# 12V_Buck_For_5V_3V3.net
KiCad netlist of a schematic drawn in Altium Designer
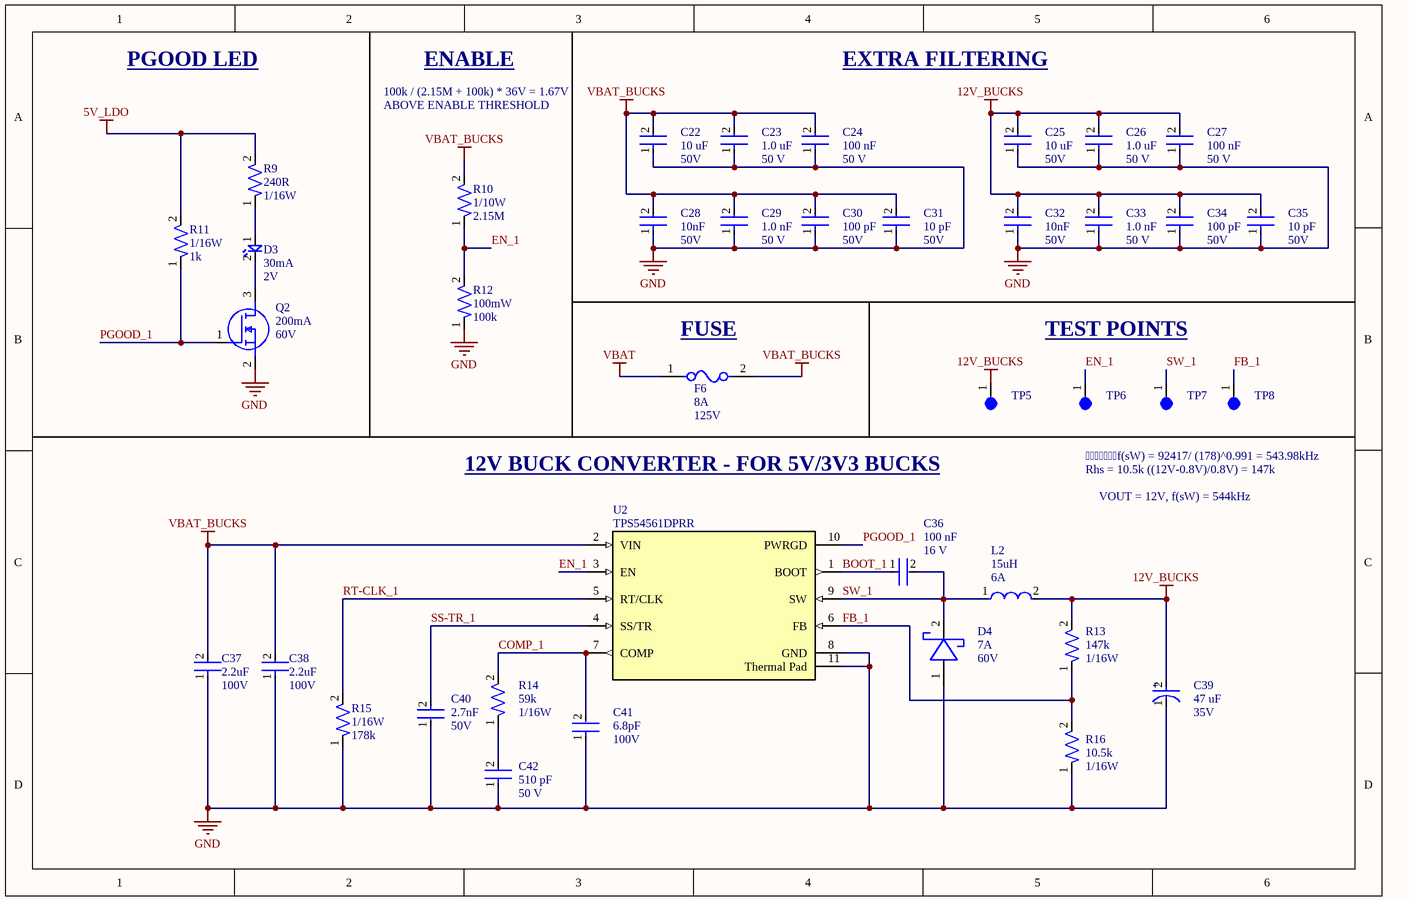
[diagram p0: 12V_Buck_For_5V_3V3.SchDoc]

(export (version "E")
  (design (tool "Eeschema 10.0.6"))
  (components
    (comp (ref "C22")
      (value "CL32B106KBJNNNE")
      (footprint "CAP-1210")
      (description "CAP CER 10UF 50V X7R 1210")
      (fields (field (name "VOLTAGE") "50V") (field (name "CAPACITANCE") "10 uF"))
      (libsource (lib "JLC_25") (part "CAP-10U-0002"))
    )
    (comp (ref "C23")
      (value "CC0805KKX7R9BB105")
      (footprint "CAP-0805")
      (description "CAP CER 1UF 50V X7R 0805")
      (fields (field (name "VOLTAGE") "50 V") (field (name "CAPACITANCE") "1.0 uF"))
      (libsource (lib "JLC_25") (part "CAP-1U-0001"))
    )
    (comp (ref "C24")
      (value "CC0805KRX7R9BB104")
      (footprint "CAP-0805")
      (description "CAP CER 0.1UF 50V X7R 0805")
      (fields (field (name "VOLTAGE RATING") "50 V") (field (name "CAPACITANCE") "100 nF"))
      (libsource (lib "JLC_25") (part "CAP-0.1U-0002"))
    )
    (comp (ref "C25")
      (value "CL32B106KBJNNNE")
      (footprint "CAP-1210")
      (description "CAP CER 10UF 50V X7R 1210")
      (fields (field (name "VOLTAGE") "50V") (field (name "CAPACITANCE") "10 uF"))
      (libsource (lib "JLC_25") (part "CAP-10U-0002"))
    )
    (comp (ref "C26")
      (value "CC0805KKX7R9BB105")
      (footprint "CAP-0805")
      (description "CAP CER 1UF 50V X7R 0805")
      (fields (field (name "VOLTAGE") "50 V") (field (name "CAPACITANCE") "1.0 uF"))
      (libsource (lib "JLC_25") (part "CAP-1U-0001"))
    )
    (comp (ref "C27")
      (value "CC0805KRX7R9BB104")
      (footprint "CAP-0805")
      (description "CAP CER 0.1UF 50V X7R 0805")
      (fields (field (name "VOLTAGE RATING") "50 V") (field (name "CAPACITANCE") "100 nF"))
      (libsource (lib "JLC_25") (part "CAP-0.1U-0002"))
    )
    (comp (ref "C28")
      (value "GRM2195C1H103JA01D")
      (footprint "CAP-0805")
      (description "CAP CER 10000PF 50V C0G/NP0 0805")
      (fields (field (name "VOLTAGE") "50V") (field (name "CAPACITANCE") "10nF"))
      (libsource (lib "JLC_25") (part "CAP-10N-0001"))
    )
    (comp (ref "C29")
      (value "CC0402KRX7R9BB102")
      (footprint "CAP-0402")
      (description "CAP CER 1000PF 50V X7R 0402")
      (fields (field (name "VOLTAGE") "50 V") (field (name "CAPACITANCE") "1.0 nF"))
      (libsource (lib "JLC_25") (part "CAP-1N-0001"))
    )
    (comp (ref "C30")
      (value "CC0402JRNPO9BN101")
      (footprint "CAP-0402")
      (description "CAP CER 100PF 50V C0G/NPO 0402")
      (fields (field (name "CAPACITANCE") "100 pF") (field (name "VOLTAGE") "50V"))
      (libsource (lib "JLC_25") (part "CAP-100P-0001"))
    )
    (comp (ref "C31")
      (value "CC0402JRNPO9BN100")
      (footprint "CAP-0402")
      (description "CAP CER 10PF 50V C0G/NPO 0402")
      (fields (field (name "CAPACITANCE") "10 pF") (field (name "VOLTAGE") "50V"))
      (libsource (lib "JLC_25") (part "CAP-10P-0001"))
    )
    (comp (ref "C32")
      (value "GRM2195C1H103JA01D")
      (footprint "CAP-0805")
      (description "CAP CER 10000PF 50V C0G/NP0 0805")
      (fields (field (name "VOLTAGE") "50V") (field (name "CAPACITANCE") "10nF"))
      (libsource (lib "JLC_25") (part "CAP-10N-0001"))
    )
    (comp (ref "C33")
      (value "CC0402KRX7R9BB102")
      (footprint "CAP-0402")
      (description "CAP CER 1000PF 50V X7R 0402")
      (fields (field (name "VOLTAGE") "50 V") (field (name "CAPACITANCE") "1.0 nF"))
      (libsource (lib "JLC_25") (part "CAP-1N-0001"))
    )
    (comp (ref "C34")
      (value "CC0402JRNPO9BN101")
      (footprint "CAP-0402")
      (description "CAP CER 100PF 50V C0G/NPO 0402")
      (fields (field (name "CAPACITANCE") "100 pF") (field (name "VOLTAGE") "50V"))
      (libsource (lib "JLC_25") (part "CAP-100P-0001"))
    )
    (comp (ref "C35")
      (value "CC0402JRNPO9BN100")
      (footprint "CAP-0402")
      (description "CAP CER 10PF 50V C0G/NPO 0402")
      (fields (field (name "CAPACITANCE") "10 pF") (field (name "VOLTAGE") "50V"))
      (libsource (lib "JLC_25") (part "CAP-10P-0001"))
    )
    (comp (ref "C36")
      (value "CC0402KRX7R7BB104")
      (footprint "CAP-0402")
      (description "CAP CER 0.1UF 16V X7R 0402")
      (fields (field (name "VOLTAGE RATING") "16 V") (field (name "CAPACITANCE") "100 nF"))
      (libsource (lib "JLC_25") (part "CAP-0.1U-0001"))
    )
    (comp (ref "C37")
      (value "CC1206KKX7R0BB225")
      (footprint "CAP-1206")
      (description "CAP CER 2.2UF 100V X7R 1206")
      (fields (field (name "CAPACITANCE") "2.2uF") (field (name "VOLTAGE") "100V"))
      (libsource (lib "JLC_25") (part "CAP-2.2U-0001"))
    )
    (comp (ref "C38")
      (value "CC1206KKX7R0BB225")
      (footprint "CAP-1206")
      (description "CAP CER 2.2UF 100V X7R 1206")
      (fields (field (name "CAPACITANCE") "2.2uF") (field (name "VOLTAGE") "100V"))
      (libsource (lib "JLC_25") (part "CAP-2.2U-0001"))
    )
    (comp (ref "C39")
      (value "EEH-ZC1V470P")
      (footprint "CAP_EEHZC1V470P")
      (description "47 µF 35 V Aluminum - Polymer Capacitors Radial, Can - SMD 60mOhm 4000 Hrs @ 125°C")
      (fields (field (name "VOLTAGE") "35V") (field (name "CAPACITANCE") "47 uF"))
      (libsource (lib "JLC_25") (part "CAP-47U-0003"))
    )
    (comp (ref "C40")
      (value "GRM2165C1H272JA01D")
      (footprint "CAP-0805")
      (description "CAP CER 2700PF 50V C0G/NP0 0805")
      (fields (field (name "VOLTAGE") "50V") (field (name "CAPACITANCE") "2.7nF"))
      (libsource (lib "JLC_25") (part "CAP-2.7N-0001"))
    )
    (comp (ref "C41")
      (value "CC0603CRNPO0BN6R8")
      (footprint "CAP-0603")
      (description "CAP CER 6.8PF 100V C0G/NPO 0603")
      (fields (field (name "VOLTAGE") "100V") (field (name "CAPACITANCE") "6.8pF"))
      (libsource (lib "JLC_25") (part "CAP-6.8P-0001"))
    )
    (comp (ref "C42")
      (value "0402N511J500CT")
      (footprint "CAP-0402")
      (description "CAP CER 510PF 50V C0G/NP0 0402")
      (fields (field (name "VOLTAGE") "50 V") (field (name "CAPACITANCE") "510 pF"))
      (libsource (lib "JLC_25") (part "CAP-510P-0001"))
    )
    (comp (ref "D3")
      (value "BL-HKC36G-AV-TRB")
      (footprint "LED-0603")
      (description "LED YELLOW CLEAR 0603 SMD")
      (fields (field (name "FORWARD CURRENT") "30mA") (field (name "FORWARD VOLTAGE") "2V"))
      (libsource (lib "JLC_25") (part "LED-0001"))
    )
    (comp (ref "D4")
      (value "PDS760-13")
      (footprint "DO-POWERDI5")
      (description "DIODE SCHOTTKY 60V 7A POWERDI5")
      (fields (field (name "FORWARD CURRENT") "7A") (field (name "REVERSE VOLTAGE (DC)") "60V"))
      (libsource (lib "JLC_25") (part "DIO-SCHOTTKY-0001"))
    )
    (comp (ref "F6")
      (value "01550900M")
      (footprint "FUSE-0001")
      (description "FUSE BLOK CARTRIDGE 125V 10A SMD")
      (fields (field (name "FUSE CURRENT") "8A") (field (name "VOLTAGE RATING") "125V"))
      (libsource (lib "JLC_25") (part "FUSE-0001"))
    )
    (comp (ref "L2")
      (value "CSAD1010-150M")
      (footprint "IND-15U-0002")
      (description "SMD MOLDING POWER CHOKE")
      (fields (field (name "INDUCTANCE") "15uH") (field (name "CURRENT RATING") "6A"))
      (libsource (lib "JLC_25") (part "IND-15U-0002-NoJLC"))
    )
    (comp (ref "Q2")
      (value "T2N7002AK,LM")
      (footprint "IC-SOT23-3")
      (description "MOSFET N-CH 60V 200MA SOT23")
      (fields (field (name "CONTINUOUS CURRENT") "200mA") (field (name "VOLTAGE") "60V"))
      (libsource (lib "JLC_25") (part "NMOS-200MA-0001"))
    )
    (comp (ref "R9")
      (value "RC0402FR-07240RL")
      (footprint "RES-0402")
      (description "240R 0.063W 1% 0402 (1005 Metric)  SMD")
      (fields
        (field (name "TOLERANCE") "1%")
        (field (name "RESISTANCE") "240R")
        (field (name "POWER") "1/16W")
      )
      (libsource (lib "JLC_25") (part "RES-240-0001"))
    )
    (comp (ref "R10")
      (value "RC0603FR-072M15L")
      (footprint "RES-0603")
      (description "RES SMD 2.15M OHM 1% 1/10W 0603")
      (fields
        (field (name "TOLERANCE") "1%")
        (field (name "POWER") "1/10W")
        (field (name "RESISTANCE") "2.15M")
      )
      (libsource (lib "JLC_25") (part "RES-2.15M-0001"))
    )
    (comp (ref "R11")
      (value "RC0402FR-071KL")
      (footprint "RES-0402")
      (description "RES 1K OHM 1% 1/16W 0402")
      (fields (field (name "TOLERANCE") "1%") (field (name "POWER") "1/16W") (field (name "RESISTANCE") "1k"))
      (libsource (lib "JLC_25") (part "RES-1k-0001"))
    )
    (comp (ref "R12")
      (value "RC0603FR-07100KL")
      (footprint "RES-0603")
      (description "RES SMD 100K OHM 1% 1/10W 0603")
      (fields
        (field (name "TOLERANCE") "1%")
        (field (name "POWER") "100mW")
        (field (name "RESISTANCE") "100k")
      )
      (libsource (lib "JLC_25") (part "RES-100k-0001"))
    )
    (comp (ref "R13")
      (value "RC0402FR-07147KL")
      (footprint "RES-0402")
      (description "RES 147K OHM 1% 1/16W 0402")
      (fields
        (field (name "TOLERANCE") "1%")
        (field (name "POWER") "1/16W")
        (field (name "RESISTANCE") "147k")
      )
      (libsource (lib "JLC_25") (part "RES-147k-0001"))
    )
    (comp (ref "R14")
      (value "RC0402FR-0759KL")
      (footprint "RES-0402")
      (description "RES 59K OHM 1% 1/16W 0402")
      (fields
        (field (name "TOLERANCE") "1%")
        (field (name "POWER") "1/16W")
        (field (name "RESISTANCE") "59k")
      )
      (libsource (lib "JLC_25") (part "RES-59k-0001"))
    )
    (comp (ref "R15")
      (value "RTT021783FTH")
      (footprint "RES-0402")
      (description "62.5mW Thick Film Resistors 50V ±100ppm/℃ ±1% 178kΩ 0402 Chip Resistor - Surface Mount ROHS")
      (fields
        (field (name "TOLERANCE") "1%")
        (field (name "POWER") "1/16W")
        (field (name "RESISTANCE") "178k")
      )
      (libsource (lib "JLC_25") (part "RES-178k-0001_1"))
    )
    (comp (ref "R16")
      (value "RC0402FR-0710K5L")
      (footprint "RES-0402")
      (description "RES 10.5K OHM 1% 1/16W 0402")
      (fields
        (field (name "TOLERANCE") "1%")
        (field (name "POWER") "1/16W")
        (field (name "RESISTANCE") "10.5k")
      )
      (libsource (lib "JLC_25") (part "RES-10.5k-0001"))
    )
    (comp (ref "TP5")
      (value "5003")
      (footprint "TEST-POINT-0001")
      (description "Oranange PC Test Point, Miniature Phoisphor Bronze Silver Plating Through Hole Mounting Type")
      (libsource (lib "*") (part "TEST-POINT-0001"))
    )
    (comp (ref "TP6")
      (value "5003")
      (footprint "TEST-POINT-0001")
      (description "Oranange PC Test Point, Miniature Phoisphor Bronze Silver Plating Through Hole Mounting Type")
      (libsource (lib "*") (part "TEST-POINT-0001"))
    )
    (comp (ref "TP7")
      (value "5003")
      (footprint "TEST-POINT-0001")
      (description "Oranange PC Test Point, Miniature Phoisphor Bronze Silver Plating Through Hole Mounting Type")
      (libsource (lib "*") (part "TEST-POINT-0001"))
    )
    (comp (ref "TP8")
      (value "5003")
      (footprint "TEST-POINT-0001")
      (description "Oranange PC Test Point, Miniature Phoisphor Bronze Silver Plating Through Hole Mounting Type")
      (libsource (lib "*") (part "TEST-POINT-0001"))
    )
    (comp (ref "U2")
      (value "TPS54561DPRR")
      (footprint "IC-10WSON")
      (description "IC REG BUCK ADJ 5A 10WSON")
      (libsource (lib "JLC_25") (part "IC-BUCK-0001"))
    )
  )
  (nets
    (net (code "1") (name "/BOOT_1") (class "Default")
      (node (ref "C36") (pin "1") (pinfunction "1_1") (pintype "passive"))
      (node (ref "U2") (pin "1") (pinfunction "BOOT_1") (pintype "output"))
    )
    (net (code "2") (name "/COMP_1") (class "Default")
      (node (ref "C41") (pin "2") (pinfunction "2_2") (pintype "passive"))
      (node (ref "R14") (pin "2") (pinfunction "2_2") (pintype "passive"))
      (node (ref "U2") (pin "7") (pinfunction "COMP_7") (pintype "output"))
    )
    (net (code "3") (name "/EN_1") (class "Default")
      (node (ref "R10") (pin "1") (pinfunction "1_1") (pintype "passive"))
      (node (ref "R12") (pin "2") (pinfunction "2_2") (pintype "passive"))
      (node (ref "TP6") (pin "1") (pinfunction "0_1") (pintype "passive"))
      (node (ref "U2") (pin "3") (pinfunction "EN_3") (pintype "input"))
    )
    (net (code "4") (name "/FB_1") (class "Default")
      (node (ref "R13") (pin "1") (pinfunction "1_1") (pintype "passive"))
      (node (ref "R16") (pin "2") (pinfunction "2_2") (pintype "passive"))
      (node (ref "TP8") (pin "1") (pinfunction "0_1") (pintype "passive"))
      (node (ref "U2") (pin "6") (pinfunction "FB_6") (pintype "input"))
    )
    (net (code "5") (name "/PGOOD_1") (class "Default")
      (node (ref "Q2") (pin "1") (pinfunction "G_1") (pintype "passive"))
      (node (ref "R11") (pin "1") (pinfunction "1_1") (pintype "passive"))
      (node (ref "U2") (pin "10") (pinfunction "PWRGD_10") (pintype "open_collector"))
    )
    (net (code "6") (name "/RT-CLK_1") (class "Default")
      (node (ref "R15") (pin "2") (pinfunction "2_2") (pintype "passive"))
      (node (ref "U2") (pin "5") (pinfunction "RT/CLK_5") (pintype "input"))
    )
    (net (code "7") (name "/SS-TR_1") (class "Default")
      (node (ref "C40") (pin "2") (pinfunction "2_2") (pintype "passive"))
      (node (ref "U2") (pin "4") (pinfunction "SS/TR_4") (pintype "input"))
    )
    (net (code "8") (name "/SW_1") (class "Default")
      (node (ref "C36") (pin "2") (pinfunction "2_2") (pintype "passive"))
      (node (ref "D4") (pin "2") (pinfunction "ANODE_2") (pintype "passive"))
      (node (ref "L2") (pin "1") (pinfunction "1_1") (pintype "passive"))
      (node (ref "TP7") (pin "1") (pinfunction "0_1") (pintype "passive"))
      (node (ref "U2") (pin "9") (pinfunction "SW_9") (pintype "input"))
    )
    (net (code "9") (name "5V_LDO") (class "Default")
      (node (ref "R11") (pin "2") (pinfunction "2_2") (pintype "passive"))
      (node (ref "R9") (pin "2") (pinfunction "2_2") (pintype "passive"))
    )
    (net (code "10") (name "12V_BUCKS") (class "Default")
      (node (ref "C25") (pin "2") (pinfunction "2_2") (pintype "passive"))
      (node (ref "C26") (pin "2") (pinfunction "2_2") (pintype "passive"))
      (node (ref "C27") (pin "2") (pinfunction "2_2") (pintype "passive"))
      (node (ref "C32") (pin "2") (pinfunction "2_2") (pintype "passive"))
      (node (ref "C33") (pin "2") (pinfunction "2_2") (pintype "passive"))
      (node (ref "C34") (pin "2") (pinfunction "2_2") (pintype "passive"))
      (node (ref "C35") (pin "2") (pinfunction "2_2") (pintype "passive"))
      (node (ref "C39") (pin "2") (pinfunction "A_2") (pintype "passive"))
      (node (ref "L2") (pin "2") (pinfunction "2_2") (pintype "passive"))
      (node (ref "R13") (pin "2") (pinfunction "2_2") (pintype "passive"))
      (node (ref "TP5") (pin "1") (pinfunction "0_1") (pintype "passive"))
    )
    (net (code "11") (name "GND") (class "Default")
      (node (ref "C22") (pin "1") (pinfunction "1_1") (pintype "passive"))
      (node (ref "C23") (pin "1") (pinfunction "1_1") (pintype "passive"))
      (node (ref "C24") (pin "1") (pinfunction "1_1") (pintype "passive"))
      (node (ref "C25") (pin "1") (pinfunction "1_1") (pintype "passive"))
      (node (ref "C26") (pin "1") (pinfunction "1_1") (pintype "passive"))
      (node (ref "C27") (pin "1") (pinfunction "1_1") (pintype "passive"))
      (node (ref "C28") (pin "1") (pinfunction "1_1") (pintype "passive"))
      (node (ref "C29") (pin "1") (pinfunction "1_1") (pintype "passive"))
      (node (ref "C30") (pin "1") (pinfunction "1_1") (pintype "passive"))
      (node (ref "C31") (pin "1") (pinfunction "1_1") (pintype "passive"))
      (node (ref "C32") (pin "1") (pinfunction "1_1") (pintype "passive"))
      (node (ref "C33") (pin "1") (pinfunction "1_1") (pintype "passive"))
      (node (ref "C34") (pin "1") (pinfunction "1_1") (pintype "passive"))
      (node (ref "C35") (pin "1") (pinfunction "1_1") (pintype "passive"))
      (node (ref "C37") (pin "1") (pinfunction "1_1") (pintype "passive"))
      (node (ref "C38") (pin "1") (pinfunction "1_1") (pintype "passive"))
      (node (ref "C39") (pin "1") (pinfunction "C_1") (pintype "passive"))
      (node (ref "C40") (pin "1") (pinfunction "1_1") (pintype "passive"))
      (node (ref "C41") (pin "1") (pinfunction "1_1") (pintype "passive"))
      (node (ref "C42") (pin "1") (pinfunction "1_1") (pintype "passive"))
      (node (ref "D4") (pin "1") (pinfunction "CATHODE_1") (pintype "passive"))
      (node (ref "Q2") (pin "2") (pinfunction "S_2") (pintype "passive"))
      (node (ref "R12") (pin "1") (pinfunction "1_1") (pintype "passive"))
      (node (ref "R15") (pin "1") (pinfunction "1_1") (pintype "passive"))
      (node (ref "R16") (pin "1") (pinfunction "1_1") (pintype "passive"))
      (node (ref "U2") (pin "11") (pinfunction "Thermal_Pad_11") (pintype "power_in"))
      (node (ref "U2") (pin "8") (pinfunction "GND_8") (pintype "power_in"))
    )
    (net (code "12") (name "Net-(C42-Pad2)") (class "Default")
      (node (ref "C42") (pin "2") (pinfunction "2_2") (pintype "passive"))
      (node (ref "R14") (pin "1") (pinfunction "1_1") (pintype "passive"))
    )
    (net (code "13") (name "Net-(D3-Pad1)") (class "Default")
      (node (ref "D3") (pin "1") (pinfunction "1_1") (pintype "passive"))
      (node (ref "R9") (pin "1") (pinfunction "1_1") (pintype "passive"))
    )
    (net (code "14") (name "Net-(Q2-D)") (class "Default")
      (node (ref "D3") (pin "2") (pinfunction "2_2") (pintype "passive"))
      (node (ref "Q2") (pin "3") (pinfunction "D_3") (pintype "passive"))
    )
    (net (code "15") (name "VBAT") (class "Default")
      (node (ref "F6") (pin "1") (pinfunction "1_1") (pintype "passive"))
    )
    (net (code "16") (name "VBAT_BUCKS") (class "Default")
      (node (ref "C22") (pin "2") (pinfunction "2_2") (pintype "passive"))
      (node (ref "C23") (pin "2") (pinfunction "2_2") (pintype "passive"))
      (node (ref "C24") (pin "2") (pinfunction "2_2") (pintype "passive"))
      (node (ref "C28") (pin "2") (pinfunction "2_2") (pintype "passive"))
      (node (ref "C29") (pin "2") (pinfunction "2_2") (pintype "passive"))
      (node (ref "C30") (pin "2") (pinfunction "2_2") (pintype "passive"))
      (node (ref "C31") (pin "2") (pinfunction "2_2") (pintype "passive"))
      (node (ref "C37") (pin "2") (pinfunction "2_2") (pintype "passive"))
      (node (ref "C38") (pin "2") (pinfunction "2_2") (pintype "passive"))
      (node (ref "F6") (pin "2") (pinfunction "2_2") (pintype "passive"))
      (node (ref "R10") (pin "2") (pinfunction "2_2") (pintype "passive"))
      (node (ref "U2") (pin "2") (pinfunction "VIN_2") (pintype "input"))
    )
  )
)
